# schemat.net
KiCad netlist of a schematic drawn in EAGLE
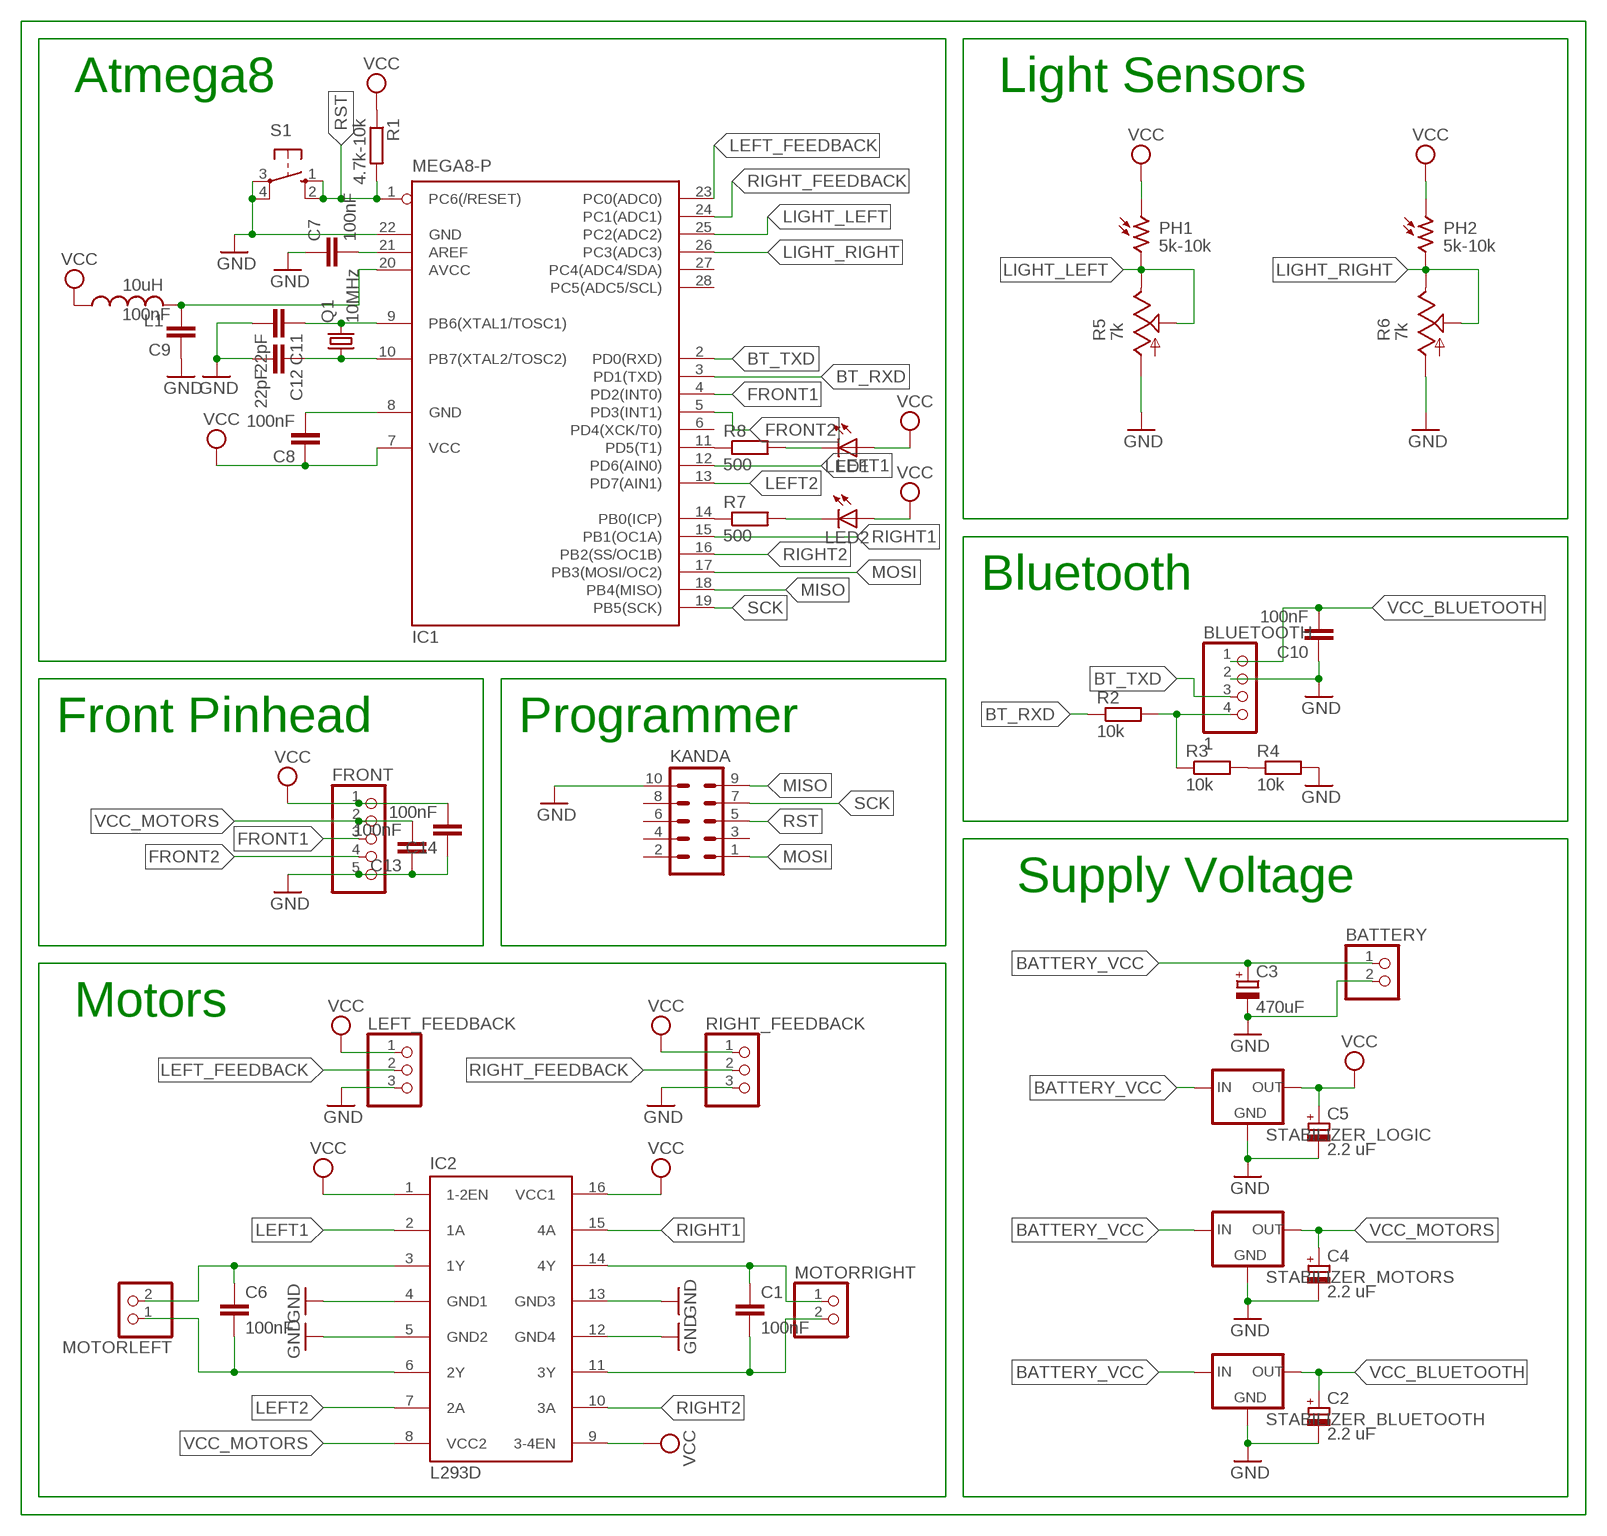
[diagram p0: schematic, sheet 1]

(export (version "E")
  (design (tool "Eeschema 10.0.6"))
  (components
    (comp (ref "BATTERY")
      (value "PINHD-1X2")
      (footprint "eagle-import:1X02")
      (libsource (lib "eagle-import") (part "PINHD-1X2"))
    )
    (comp (ref "BLUETOOTH")
      (value "1")
      (footprint "eagle-import:1X04")
      (libsource (lib "eagle-import") (part "PINHD-1X4"))
    )
    (comp (ref "C1")
      (value "100nF")
      (footprint "eagle-import:C2.5-3")
      (libsource (lib "eagle-import") (part "C2,5-3"))
    )
    (comp (ref "C2")
      (value "2.2 uF")
      (footprint "eagle-import:E1,8-4")
      (libsource (lib "eagle-import") (part "CPOL-EUE1.8-4"))
    )
    (comp (ref "C3")
      (value "470uF")
      (footprint "eagle-import:E3,5-8")
      (libsource (lib "eagle-import") (part "CPOL-EUE3.5-8"))
    )
    (comp (ref "C4")
      (value "2.2 uF")
      (footprint "eagle-import:E1,8-4")
      (libsource (lib "eagle-import") (part "CPOL-EUE1.8-4"))
    )
    (comp (ref "C5")
      (value "2.2 uF")
      (footprint "eagle-import:E1,8-4")
      (libsource (lib "eagle-import") (part "CPOL-EUE1.8-4"))
    )
    (comp (ref "C6")
      (value "100nF")
      (footprint "eagle-import:C2.5-3")
      (libsource (lib "eagle-import") (part "C2,5-3"))
    )
    (comp (ref "C7")
      (value "100nF")
      (footprint "eagle-import:C2.5-3")
      (libsource (lib "eagle-import") (part "C2,5-3"))
    )
    (comp (ref "C8")
      (value "100nF")
      (footprint "eagle-import:C2.5-3")
      (libsource (lib "eagle-import") (part "C2,5-3"))
    )
    (comp (ref "C9")
      (value "100nF")
      (footprint "eagle-import:C2.5-3")
      (libsource (lib "eagle-import") (part "C2,5-3"))
    )
    (comp (ref "C10")
      (value "100nF")
      (footprint "eagle-import:C2.5-3")
      (libsource (lib "eagle-import") (part "C2,5-3"))
    )
    (comp (ref "C11")
      (value "22pF")
      (footprint "eagle-import:C2.5-3")
      (libsource (lib "eagle-import") (part "C2,5-3"))
    )
    (comp (ref "C12")
      (value "22pF")
      (footprint "eagle-import:C2.5-3")
      (libsource (lib "eagle-import") (part "C2,5-3"))
    )
    (comp (ref "C13")
      (value "100nF")
      (footprint "eagle-import:C2.5-3")
      (libsource (lib "eagle-import") (part "C2,5-3"))
    )
    (comp (ref "C14")
      (value "100nF")
      (footprint "eagle-import:C2.5-3")
      (libsource (lib "eagle-import") (part "C2,5-3"))
    )
    (comp (ref "FRONT")
      (value "PINHD-1X5")
      (footprint "eagle-import:1X05")
      (libsource (lib "eagle-import") (part "PINHD-1X5"))
    )
    (comp (ref "IC1")
      (value "MEGA8-P")
      (footprint "eagle-import:DIL28-3")
      (libsource (lib "eagle-import") (part "MEGA8-P"))
    )
    (comp (ref "IC2")
      (value "L293D")
      (footprint "eagle-import:DIL16")
      (libsource (lib "eagle-import") (part "L293D"))
    )
    (comp (ref "KANDA")
      (value "ML10")
      (footprint "eagle-import:ML10")
      (libsource (lib "eagle-import") (part "ML10"))
    )
    (comp (ref "L1")
      (value "10uH")
      (footprint "eagle-import:0204_7")
      (libsource (lib "eagle-import") (part "L-US0204/7"))
    )
    (comp (ref "LED1")
      (value "LEDSFH480")
      (footprint "eagle-import:SFH480")
      (libsource (lib "eagle-import") (part "LEDSFH480"))
    )
    (comp (ref "LED2")
      (value "LEDSFH480")
      (footprint "eagle-import:SFH480")
      (libsource (lib "eagle-import") (part "LEDSFH480"))
    )
    (comp (ref "LEFT_FEEDBACK")
      (value "PINHD-1X3")
      (footprint "eagle-import:1X03")
      (libsource (lib "eagle-import") (part "PINHD-1X3"))
    )
    (comp (ref "MOTORLEFT")
      (value "PINHD-1X2")
      (footprint "eagle-import:1X02")
      (libsource (lib "eagle-import") (part "PINHD-1X2"))
    )
    (comp (ref "MOTORRIGHT")
      (value "PINHD-1X2")
      (footprint "eagle-import:1X02")
      (libsource (lib "eagle-import") (part "PINHD-1X2"))
    )
    (comp (ref "PH1")
      (value "5k-10k")
      (footprint "eagle-import:VT800")
      (libsource (lib "eagle-import") (part "VT83N2"))
    )
    (comp (ref "PH2")
      (value "5k-10k")
      (footprint "eagle-import:VT800")
      (libsource (lib "eagle-import") (part "VT83N2"))
    )
    (comp (ref "Q1")
      (value "10MHz")
      (footprint "eagle-import:HC49U-V")
      (libsource (lib "eagle-import") (part "CRYSTALHC49U-V"))
    )
    (comp (ref "R1")
      (value "4.7k-10k")
      (footprint "eagle-import:0204_7")
      (libsource (lib "eagle-import") (part "R-EU_0204/7"))
    )
    (comp (ref "R2")
      (value "10k")
      (footprint "eagle-import:0204_7")
      (libsource (lib "eagle-import") (part "R-EU_0204/7"))
    )
    (comp (ref "R3")
      (value "10k")
      (footprint "eagle-import:0204_7")
      (libsource (lib "eagle-import") (part "R-EU_0204/7"))
    )
    (comp (ref "R4")
      (value "10k")
      (footprint "eagle-import:0204_7")
      (libsource (lib "eagle-import") (part "R-EU_0204/7"))
    )
    (comp (ref "R5")
      (value "7k")
      (footprint "eagle-import:CA6V")
      (libsource (lib "eagle-import") (part "TRIM_US-CA6V"))
    )
    (comp (ref "R6")
      (value "7k")
      (footprint "eagle-import:CA6V")
      (libsource (lib "eagle-import") (part "TRIM_US-CA6V"))
    )
    (comp (ref "R7")
      (value "500")
      (footprint "eagle-import:0204_7")
      (libsource (lib "eagle-import") (part "R-EU_0204/7"))
    )
    (comp (ref "R8")
      (value "500")
      (footprint "eagle-import:0204_7")
      (libsource (lib "eagle-import") (part "R-EU_0204/7"))
    )
    (comp (ref "RIGHT_FEEDBACK")
      (value "PINHD-1X3")
      (footprint "eagle-import:1X03")
      (libsource (lib "eagle-import") (part "PINHD-1X3"))
    )
    (comp (ref "S1")
      (value "10-XX")
      (footprint "eagle-import:B3F-10XX")
      (fields (field (name "MPN") "B3F-1000"))
      (libsource (lib "eagle-import") (part "10-XX"))
    )
    (comp (ref "STABILIZER_BLUETOOTH")
      (value "78XXS")
      (footprint "eagle-import:78XXS")
      (libsource (lib "eagle-import") (part "78XXS"))
    )
    (comp (ref "STABILIZER_LOGIC")
      (value "78XXS")
      (footprint "eagle-import:78XXS")
      (libsource (lib "eagle-import") (part "78XXS"))
    )
    (comp (ref "STABILIZER_MOTORS")
      (value "78XXS")
      (footprint "eagle-import:78XXS")
      (libsource (lib "eagle-import") (part "78XXS"))
    )
  )
  (nets
    (net (code "1") (name "BATTERY_VCC") (class "Default")
      (node (ref "BATTERY") (pin "1") (pinfunction "1_1") (pintype "passive"))
      (node (ref "C3") (pin "+") (pinfunction "+_+") (pintype "passive"))
      (node (ref "STABILIZER_BLUETOOTH") (pin "IN") (pinfunction "IN_IN") (pintype "input"))
      (node (ref "STABILIZER_LOGIC") (pin "IN") (pinfunction "IN_IN") (pintype "input"))
      (node (ref "STABILIZER_MOTORS") (pin "IN") (pinfunction "IN_IN") (pintype "input"))
    )
    (net (code "2") (name "BT_RXD") (class "Default")
      (node (ref "IC1") (pin "3") (pinfunction "PD1(TXD)_3") (pintype "bidirectional"))
      (node (ref "R2") (pin "1") (pinfunction "1_1") (pintype "passive"))
    )
    (net (code "3") (name "BT_TXD") (class "Default")
      (node (ref "BLUETOOTH") (pin "3") (pinfunction "3_3") (pintype "passive"))
      (node (ref "IC1") (pin "2") (pinfunction "PD0(RXD)_2") (pintype "bidirectional"))
    )
    (net (code "4") (name "FRONT1") (class "Default")
      (node (ref "FRONT") (pin "3") (pinfunction "3_3") (pintype "passive"))
      (node (ref "IC1") (pin "4") (pinfunction "PD2(INT0)_4") (pintype "bidirectional"))
    )
    (net (code "5") (name "FRONT2") (class "Default")
      (node (ref "FRONT") (pin "4") (pinfunction "4_4") (pintype "passive"))
      (node (ref "IC1") (pin "5") (pinfunction "PD3(INT1)_5") (pintype "bidirectional"))
    )
    (net (code "6") (name "GND") (class "Default")
      (node (ref "BATTERY") (pin "2") (pinfunction "2_2") (pintype "passive"))
      (node (ref "BLUETOOTH") (pin "2") (pinfunction "2_2") (pintype "passive"))
      (node (ref "C10") (pin "1") (pinfunction "1_1") (pintype "passive"))
      (node (ref "C11") (pin "2") (pinfunction "2_2") (pintype "passive"))
      (node (ref "C12") (pin "2") (pinfunction "2_2") (pintype "passive"))
      (node (ref "C13") (pin "1") (pinfunction "1_1") (pintype "passive"))
      (node (ref "C14") (pin "1") (pinfunction "1_1") (pintype "passive"))
      (node (ref "C2") (pin "-") (pinfunction "-_-") (pintype "passive"))
      (node (ref "C3") (pin "-") (pinfunction "-_-") (pintype "passive"))
      (node (ref "C4") (pin "-") (pinfunction "-_-") (pintype "passive"))
      (node (ref "C5") (pin "-") (pinfunction "-_-") (pintype "passive"))
      (node (ref "C7") (pin "1") (pinfunction "1_1") (pintype "passive"))
      (node (ref "C9") (pin "1") (pinfunction "1_1") (pintype "passive"))
      (node (ref "FRONT") (pin "5") (pinfunction "5_5") (pintype "passive"))
      (node (ref "IC1") (pin "22") (pinfunction "GND_22") (pintype "power_in"))
      (node (ref "IC2") (pin "12") (pinfunction "GND4_12") (pintype "power_in"))
      (node (ref "IC2") (pin "13") (pinfunction "GND3_13") (pintype "power_in"))
      (node (ref "IC2") (pin "4") (pinfunction "GND1_4") (pintype "power_in"))
      (node (ref "IC2") (pin "5") (pinfunction "GND2_5") (pintype "power_in"))
      (node (ref "KANDA") (pin "10") (pinfunction "10_10") (pintype "passive"))
      (node (ref "LEFT_FEEDBACK") (pin "3") (pinfunction "3_3") (pintype "passive"))
      (node (ref "R4") (pin "2") (pinfunction "2_2") (pintype "passive"))
      (node (ref "R5") (pin "A") (pinfunction "A_A") (pintype "passive"))
      (node (ref "R6") (pin "A") (pinfunction "A_A") (pintype "passive"))
      (node (ref "RIGHT_FEEDBACK") (pin "3") (pinfunction "3_3") (pintype "passive"))
      (node (ref "S1") (pin "3") (pinfunction "P_3") (pintype "passive"))
      (node (ref "S1") (pin "4") (pinfunction "P1_4") (pintype "passive"))
      (node (ref "STABILIZER_BLUETOOTH") (pin "GND") (pinfunction "GND_GND") (pintype "input"))
      (node (ref "STABILIZER_LOGIC") (pin "GND") (pinfunction "GND_GND") (pintype "input"))
      (node (ref "STABILIZER_MOTORS") (pin "GND") (pinfunction "GND_GND") (pintype "input"))
    )
    (net (code "7") (name "LEFT1") (class "Default")
      (node (ref "IC1") (pin "12") (pinfunction "PD6(AIN0)_12") (pintype "bidirectional"))
      (node (ref "IC2") (pin "2") (pinfunction "1A_2") (pintype "input"))
    )
    (net (code "8") (name "LEFT2") (class "Default")
      (node (ref "IC1") (pin "13") (pinfunction "PD7(AIN1)_13") (pintype "bidirectional"))
      (node (ref "IC2") (pin "7") (pinfunction "2A_7") (pintype "input"))
    )
    (net (code "9") (name "LEFT_FEEDBACK") (class "Default")
      (node (ref "IC1") (pin "23") (pinfunction "PC0(ADC0)_23") (pintype "bidirectional"))
      (node (ref "LEFT_FEEDBACK") (pin "2") (pinfunction "2_2") (pintype "passive"))
    )
    (net (code "10") (name "LIGHT_LEFT") (class "Default")
      (node (ref "IC1") (pin "25") (pinfunction "PC2(ADC2)_25") (pintype "bidirectional"))
      (node (ref "PH1") (pin "2") (pinfunction "2_2") (pintype "passive"))
      (node (ref "R5") (pin "E") (pinfunction "E_E") (pintype "passive"))
      (node (ref "R5") (pin "S") (pinfunction "S_S") (pintype "passive"))
    )
    (net (code "11") (name "LIGHT_RIGHT") (class "Default")
      (node (ref "IC1") (pin "26") (pinfunction "PC3(ADC3)_26") (pintype "bidirectional"))
      (node (ref "PH2") (pin "2") (pinfunction "2_2") (pintype "passive"))
      (node (ref "R6") (pin "E") (pinfunction "E_E") (pintype "passive"))
      (node (ref "R6") (pin "S") (pinfunction "S_S") (pintype "passive"))
    )
    (net (code "12") (name "MISO") (class "Default")
      (node (ref "IC1") (pin "18") (pinfunction "PB4(MISO)_18") (pintype "bidirectional"))
      (node (ref "KANDA") (pin "9") (pinfunction "9_9") (pintype "passive"))
    )
    (net (code "13") (name "MOSI") (class "Default")
      (node (ref "IC1") (pin "17") (pinfunction "PB3(MOSI/OC2)_17") (pintype "bidirectional"))
      (node (ref "KANDA") (pin "1") (pinfunction "1_1") (pintype "passive"))
    )
    (net (code "14") (name "Net-(BLUETOOTH-Pad4)") (class "Default")
      (node (ref "BLUETOOTH") (pin "4") (pinfunction "4_4") (pintype "passive"))
      (node (ref "R2") (pin "2") (pinfunction "2_2") (pintype "passive"))
      (node (ref "R3") (pin "1") (pinfunction "1_1") (pintype "passive"))
    )
    (net (code "15") (name "Net-(C8-Pad2)") (class "Default")
      (node (ref "C8") (pin "2") (pinfunction "2_2") (pintype "passive"))
      (node (ref "IC1") (pin "8") (pinfunction "GND_8") (pintype "power_in"))
    )
    (net (code "16") (name "Net-(IC1-AREF)") (class "Default")
      (node (ref "C7") (pin "2") (pinfunction "2_2") (pintype "passive"))
      (node (ref "IC1") (pin "21") (pinfunction "AREF_21") (pintype "passive"))
    )
    (net (code "17") (name "Net-(IC1-AVCC)") (class "Default")
      (node (ref "C9") (pin "2") (pinfunction "2_2") (pintype "passive"))
      (node (ref "IC1") (pin "20") (pinfunction "AVCC_20") (pintype "power_in"))
      (node (ref "L1") (pin "2") (pinfunction "2_2") (pintype "passive"))
    )
    (net (code "18") (name "Net-(IC1-PB0(ICP))") (class "Default")
      (node (ref "IC1") (pin "14") (pinfunction "PB0(ICP)_14") (pintype "bidirectional"))
      (node (ref "R7") (pin "1") (pinfunction "1_1") (pintype "passive"))
    )
    (net (code "19") (name "Net-(IC1-PB6(XTAL1{slash}TOSC1))") (class "Default")
      (node (ref "C11") (pin "1") (pinfunction "1_1") (pintype "passive"))
      (node (ref "IC1") (pin "9") (pinfunction "PB6(XTAL1/TOSC1)_9") (pintype "bidirectional"))
      (node (ref "Q1") (pin "2") (pinfunction "2_2") (pintype "passive"))
    )
    (net (code "20") (name "Net-(IC1-PB7(XTAL2{slash}TOSC2))") (class "Default")
      (node (ref "C12") (pin "1") (pinfunction "1_1") (pintype "passive"))
      (node (ref "IC1") (pin "10") (pinfunction "PB7(XTAL2/TOSC2)_10") (pintype "bidirectional"))
      (node (ref "Q1") (pin "1") (pinfunction "1_1") (pintype "passive"))
    )
    (net (code "21") (name "Net-(IC1-PD5(T1))") (class "Default")
      (node (ref "IC1") (pin "11") (pinfunction "PD5(T1)_11") (pintype "bidirectional"))
      (node (ref "R8") (pin "1") (pinfunction "1_1") (pintype "passive"))
    )
    (net (code "22") (name "Net-(IC2-1Y)") (class "Default")
      (node (ref "C6") (pin "1") (pinfunction "1_1") (pintype "passive"))
      (node (ref "IC2") (pin "3") (pinfunction "1Y_3") (pintype "output"))
      (node (ref "MOTORLEFT") (pin "2") (pinfunction "2_2") (pintype "passive"))
    )
    (net (code "23") (name "Net-(IC2-2Y)") (class "Default")
      (node (ref "C6") (pin "2") (pinfunction "2_2") (pintype "passive"))
      (node (ref "IC2") (pin "6") (pinfunction "2Y_6") (pintype "output"))
      (node (ref "MOTORLEFT") (pin "1") (pinfunction "1_1") (pintype "passive"))
    )
    (net (code "24") (name "Net-(IC2-3Y)") (class "Default")
      (node (ref "C1") (pin "2") (pinfunction "2_2") (pintype "passive"))
      (node (ref "IC2") (pin "11") (pinfunction "3Y_11") (pintype "output"))
      (node (ref "MOTORRIGHT") (pin "2") (pinfunction "2_2") (pintype "passive"))
    )
    (net (code "25") (name "Net-(IC2-4Y)") (class "Default")
      (node (ref "C1") (pin "1") (pinfunction "1_1") (pintype "passive"))
      (node (ref "IC2") (pin "14") (pinfunction "4Y_14") (pintype "output"))
      (node (ref "MOTORRIGHT") (pin "1") (pinfunction "1_1") (pintype "passive"))
    )
    (net (code "26") (name "Net-(LED1-C)") (class "Default")
      (node (ref "LED1") (pin "K") (pinfunction "C_K") (pintype "passive"))
      (node (ref "R8") (pin "2") (pinfunction "2_2") (pintype "passive"))
    )
    (net (code "27") (name "Net-(LED2-C)") (class "Default")
      (node (ref "LED2") (pin "K") (pinfunction "C_K") (pintype "passive"))
      (node (ref "R7") (pin "2") (pinfunction "2_2") (pintype "passive"))
    )
    (net (code "28") (name "Net-(R3-Pad2)") (class "Default")
      (node (ref "R3") (pin "2") (pinfunction "2_2") (pintype "passive"))
      (node (ref "R4") (pin "1") (pinfunction "1_1") (pintype "passive"))
    )
    (net (code "29") (name "RIGHT1") (class "Default")
      (node (ref "IC1") (pin "15") (pinfunction "PB1(OC1A)_15") (pintype "bidirectional"))
      (node (ref "IC2") (pin "15") (pinfunction "4A_15") (pintype "input"))
    )
    (net (code "30") (name "RIGHT2") (class "Default")
      (node (ref "IC1") (pin "16") (pinfunction "PB2(SS/OC1B)_16") (pintype "bidirectional"))
      (node (ref "IC2") (pin "10") (pinfunction "3A_10") (pintype "input"))
    )
    (net (code "31") (name "RIGHT_FEEDBACK") (class "Default")
      (node (ref "IC1") (pin "24") (pinfunction "PC1(ADC1)_24") (pintype "bidirectional"))
      (node (ref "RIGHT_FEEDBACK") (pin "2") (pinfunction "2_2") (pintype "passive"))
    )
    (net (code "32") (name "RST") (class "Default")
      (node (ref "IC1") (pin "1") (pinfunction "PC6(/RESET)_1") (pintype "bidirectional"))
      (node (ref "KANDA") (pin "5") (pinfunction "5_5") (pintype "passive"))
      (node (ref "R1") (pin "2") (pinfunction "2_2") (pintype "passive"))
      (node (ref "S1") (pin "1") (pinfunction "S_1") (pintype "passive"))
      (node (ref "S1") (pin "2") (pinfunction "S1_2") (pintype "passive"))
    )
    (net (code "33") (name "SCK") (class "Default")
      (node (ref "IC1") (pin "19") (pinfunction "PB5(SCK)_19") (pintype "bidirectional"))
      (node (ref "KANDA") (pin "7") (pinfunction "7_7") (pintype "passive"))
    )
    (net (code "34") (name "VCC") (class "Default")
      (node (ref "C14") (pin "2") (pinfunction "2_2") (pintype "passive"))
      (node (ref "C5") (pin "+") (pinfunction "+_+") (pintype "passive"))
      (node (ref "C8") (pin "1") (pinfunction "1_1") (pintype "passive"))
      (node (ref "FRONT") (pin "1") (pinfunction "1_1") (pintype "passive"))
      (node (ref "IC1") (pin "7") (pinfunction "VCC_7") (pintype "power_in"))
      (node (ref "IC2") (pin "1") (pinfunction "1-2EN_1") (pintype "input"))
      (node (ref "IC2") (pin "16") (pinfunction "VCC1_16") (pintype "power_in"))
      (node (ref "IC2") (pin "9") (pinfunction "3-4EN_9") (pintype "input"))
      (node (ref "L1") (pin "1") (pinfunction "1_1") (pintype "passive"))
      (node (ref "LED1") (pin "A") (pinfunction "A_A") (pintype "passive"))
      (node (ref "LED2") (pin "A") (pinfunction "A_A") (pintype "passive"))
      (node (ref "LEFT_FEEDBACK") (pin "1") (pinfunction "1_1") (pintype "passive"))
      (node (ref "PH1") (pin "1") (pinfunction "1_1") (pintype "passive"))
      (node (ref "PH2") (pin "1") (pinfunction "1_1") (pintype "passive"))
      (node (ref "R1") (pin "1") (pinfunction "1_1") (pintype "passive"))
      (node (ref "RIGHT_FEEDBACK") (pin "1") (pinfunction "1_1") (pintype "passive"))
      (node (ref "STABILIZER_LOGIC") (pin "OUT") (pinfunction "OUT_OUT") (pintype "passive"))
    )
    (net (code "35") (name "VCC_BLUETOOTH") (class "Default")
      (node (ref "BLUETOOTH") (pin "1") (pinfunction "1_1") (pintype "passive"))
      (node (ref "C10") (pin "2") (pinfunction "2_2") (pintype "passive"))
      (node (ref "C2") (pin "+") (pinfunction "+_+") (pintype "passive"))
      (node (ref "STABILIZER_BLUETOOTH") (pin "OUT") (pinfunction "OUT_OUT") (pintype "passive"))
    )
    (net (code "36") (name "VCC_MOTORS") (class "Default")
      (node (ref "C13") (pin "2") (pinfunction "2_2") (pintype "passive"))
      (node (ref "C4") (pin "+") (pinfunction "+_+") (pintype "passive"))
      (node (ref "FRONT") (pin "2") (pinfunction "2_2") (pintype "passive"))
      (node (ref "IC2") (pin "8") (pinfunction "VCC2_8") (pintype "power_in"))
      (node (ref "STABILIZER_MOTORS") (pin "OUT") (pinfunction "OUT_OUT") (pintype "passive"))
    )
    (net (code "37") (name "unconnected-(IC1-PC4(ADC4{slash}SDA)-Pad27)") (class "Default")
      (node (ref "IC1") (pin "27") (pinfunction "PC4(ADC4/SDA)_27") (pintype "bidirectional"))
    )
    (net (code "38") (name "unconnected-(IC1-PC5(ADC5{slash}SCL)-Pad28)") (class "Default")
      (node (ref "IC1") (pin "28") (pinfunction "PC5(ADC5/SCL)_28") (pintype "bidirectional"))
    )
    (net (code "39") (name "unconnected-(IC1-PD4(XCK{slash}T0)-Pad6)") (class "Default")
      (node (ref "IC1") (pin "6") (pinfunction "PD4(XCK/T0)_6") (pintype "bidirectional"))
    )
    (net (code "40") (name "unconnected-(KANDA-Pad2)") (class "Default")
      (node (ref "KANDA") (pin "2") (pinfunction "2_2") (pintype "passive"))
    )
    (net (code "41") (name "unconnected-(KANDA-Pad3)") (class "Default")
      (node (ref "KANDA") (pin "3") (pinfunction "3_3") (pintype "passive"))
    )
    (net (code "42") (name "unconnected-(KANDA-Pad4)") (class "Default")
      (node (ref "KANDA") (pin "4") (pinfunction "4_4") (pintype "passive"))
    )
    (net (code "43") (name "unconnected-(KANDA-Pad6)") (class "Default")
      (node (ref "KANDA") (pin "6") (pinfunction "6_6") (pintype "passive"))
    )
    (net (code "44") (name "unconnected-(KANDA-Pad8)") (class "Default")
      (node (ref "KANDA") (pin "8") (pinfunction "8_8") (pintype "passive"))
    )
  )
)
